# W061B.net
KiCad netlist of a schematic drawn in EAGLE
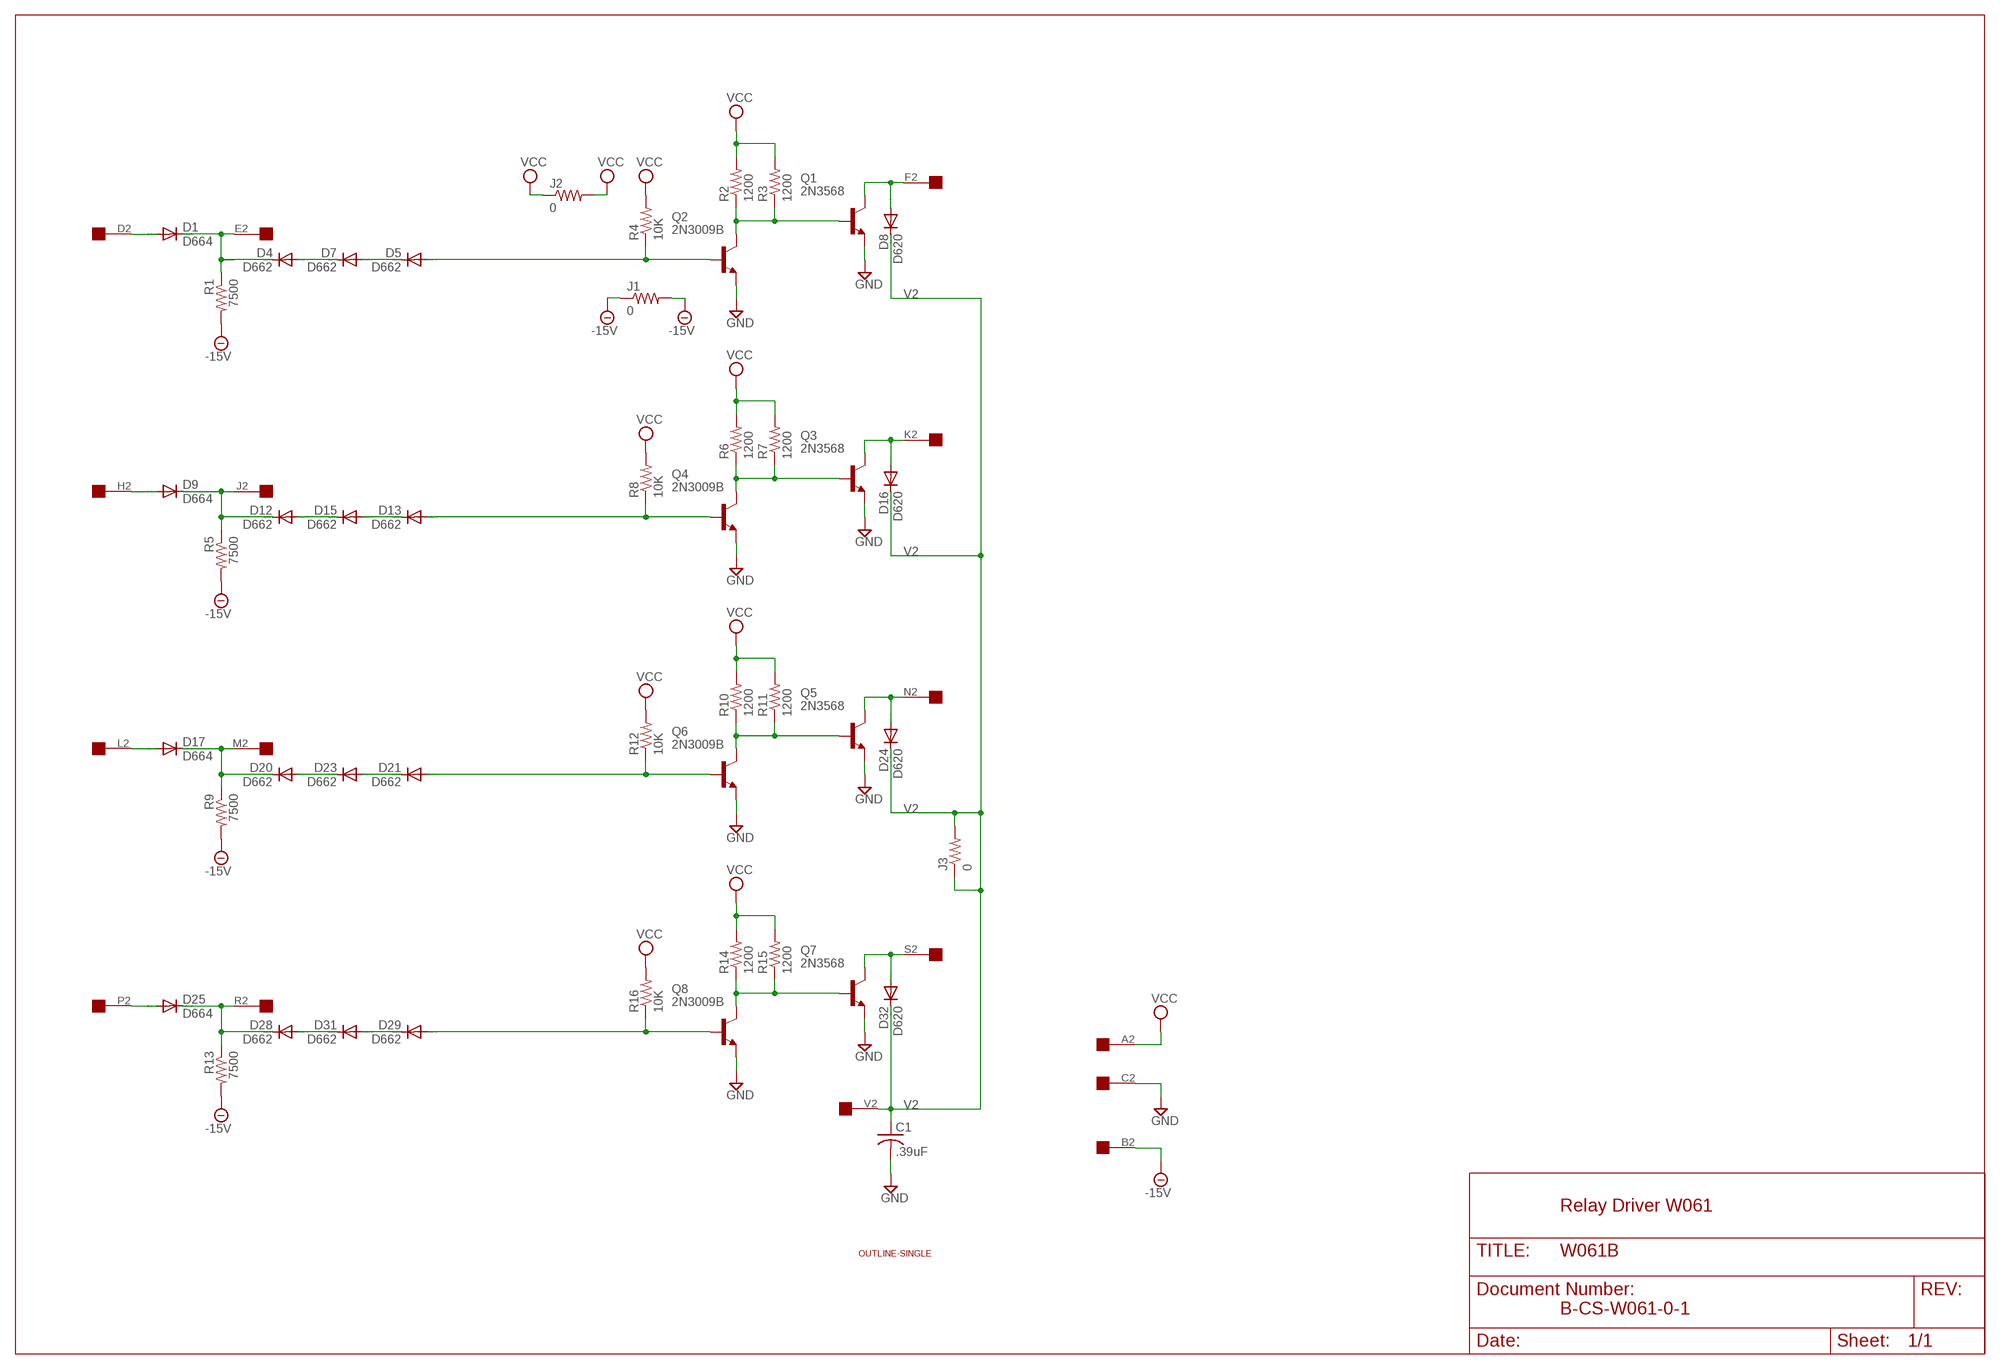
[diagram p0: schematic, sheet 1]

(export (version "E")
  (design (tool "Eeschema 10.0.6"))
  (components
    (comp (ref "C1")
      (value ".39uF")
      (footprint "eagle-import:C375-155X418")
      (libsource (lib "eagle-import") (part "C-US375-155X418"))
    )
    (comp (ref "D1")
      (value "D664")
      (footprint "eagle-import:DO35-10")
      (libsource (lib "eagle-import") (part "DIODE-DO35-10"))
    )
    (comp (ref "D4")
      (value "D662")
      (footprint "eagle-import:DO35-10")
      (libsource (lib "eagle-import") (part "DIODE-DO35-10"))
    )
    (comp (ref "D5")
      (value "D662")
      (footprint "eagle-import:DO35-10")
      (libsource (lib "eagle-import") (part "DIODE-DO35-10"))
    )
    (comp (ref "D7")
      (value "D662")
      (footprint "eagle-import:DO35-10")
      (libsource (lib "eagle-import") (part "DIODE-DO35-10"))
    )
    (comp (ref "D8")
      (value "D620")
      (footprint "eagle-import:DO35-10")
      (libsource (lib "eagle-import") (part "DIODE-DO35-10"))
    )
    (comp (ref "D9")
      (value "D664")
      (footprint "eagle-import:DO35-10")
      (libsource (lib "eagle-import") (part "DIODE-DO35-10"))
    )
    (comp (ref "D12")
      (value "D662")
      (footprint "eagle-import:DO35-10")
      (libsource (lib "eagle-import") (part "DIODE-DO35-10"))
    )
    (comp (ref "D13")
      (value "D662")
      (footprint "eagle-import:DO35-10")
      (libsource (lib "eagle-import") (part "DIODE-DO35-10"))
    )
    (comp (ref "D15")
      (value "D662")
      (footprint "eagle-import:DO35-10")
      (libsource (lib "eagle-import") (part "DIODE-DO35-10"))
    )
    (comp (ref "D16")
      (value "D620")
      (footprint "eagle-import:DO35-10")
      (libsource (lib "eagle-import") (part "DIODE-DO35-10"))
    )
    (comp (ref "D17")
      (value "D664")
      (footprint "eagle-import:DO35-10")
      (libsource (lib "eagle-import") (part "DIODE-DO35-10"))
    )
    (comp (ref "D20")
      (value "D662")
      (footprint "eagle-import:DO35-10")
      (libsource (lib "eagle-import") (part "DIODE-DO35-10"))
    )
    (comp (ref "D21")
      (value "D662")
      (footprint "eagle-import:DO35-10")
      (libsource (lib "eagle-import") (part "DIODE-DO35-10"))
    )
    (comp (ref "D23")
      (value "D662")
      (footprint "eagle-import:DO35-10")
      (libsource (lib "eagle-import") (part "DIODE-DO35-10"))
    )
    (comp (ref "D24")
      (value "D620")
      (footprint "eagle-import:DO35-10")
      (libsource (lib "eagle-import") (part "DIODE-DO35-10"))
    )
    (comp (ref "D25")
      (value "D664")
      (footprint "eagle-import:DO35-10")
      (libsource (lib "eagle-import") (part "DIODE-DO35-10"))
    )
    (comp (ref "D28")
      (value "D662")
      (footprint "eagle-import:DO35-10")
      (libsource (lib "eagle-import") (part "DIODE-DO35-10"))
    )
    (comp (ref "D29")
      (value "D662")
      (footprint "eagle-import:DO35-10")
      (libsource (lib "eagle-import") (part "DIODE-DO35-10"))
    )
    (comp (ref "D31")
      (value "D662")
      (footprint "eagle-import:DO35-10")
      (libsource (lib "eagle-import") (part "DIODE-DO35-10"))
    )
    (comp (ref "D32")
      (value "D620")
      (footprint "eagle-import:DO35-10")
      (libsource (lib "eagle-import") (part "DIODE-DO35-10"))
    )
    (comp (ref "J1")
      (value "0")
      (footprint "eagle-import:0207_10")
      (libsource (lib "eagle-import") (part "R-US_0207/10"))
    )
    (comp (ref "J2")
      (value "0")
      (footprint "eagle-import:0207_10")
      (libsource (lib "eagle-import") (part "R-US_0207/10"))
    )
    (comp (ref "J3")
      (value "0")
      (footprint "eagle-import:0207_10")
      (libsource (lib "eagle-import") (part "R-US_0207/10"))
    )
    (comp (ref "Q1")
      (value "2N3568")
      (footprint "eagle-import:TO5")
      (libsource (lib "eagle-import") (part "-NPN-TO5"))
    )
    (comp (ref "Q2")
      (value "2N3009B")
      (footprint "eagle-import:TO5")
      (libsource (lib "eagle-import") (part "-NPN-TO5"))
    )
    (comp (ref "Q3")
      (value "2N3568")
      (footprint "eagle-import:TO5")
      (libsource (lib "eagle-import") (part "-NPN-TO5"))
    )
    (comp (ref "Q4")
      (value "2N3009B")
      (footprint "eagle-import:TO5")
      (libsource (lib "eagle-import") (part "-NPN-TO5"))
    )
    (comp (ref "Q5")
      (value "2N3568")
      (footprint "eagle-import:TO5")
      (libsource (lib "eagle-import") (part "-NPN-TO5"))
    )
    (comp (ref "Q6")
      (value "2N3009B")
      (footprint "eagle-import:TO5")
      (libsource (lib "eagle-import") (part "-NPN-TO5"))
    )
    (comp (ref "Q7")
      (value "2N3568")
      (footprint "eagle-import:TO5")
      (libsource (lib "eagle-import") (part "-NPN-TO5"))
    )
    (comp (ref "Q8")
      (value "2N3009B")
      (footprint "eagle-import:TO5")
      (libsource (lib "eagle-import") (part "-NPN-TO5"))
    )
    (comp (ref "R1")
      (value "7500")
      (footprint "eagle-import:0207_10")
      (libsource (lib "eagle-import") (part "R-US_0207/10"))
    )
    (comp (ref "R2")
      (value "1200")
      (footprint "eagle-import:0207_10")
      (libsource (lib "eagle-import") (part "R-US_0207/10"))
    )
    (comp (ref "R3")
      (value "1200")
      (footprint "eagle-import:0207_10")
      (libsource (lib "eagle-import") (part "R-US_0207/10"))
    )
    (comp (ref "R4")
      (value "10K")
      (footprint "eagle-import:0207_10")
      (libsource (lib "eagle-import") (part "R-US_0207/10"))
    )
    (comp (ref "R5")
      (value "7500")
      (footprint "eagle-import:0207_10")
      (libsource (lib "eagle-import") (part "R-US_0207/10"))
    )
    (comp (ref "R6")
      (value "1200")
      (footprint "eagle-import:0207_10")
      (libsource (lib "eagle-import") (part "R-US_0207/10"))
    )
    (comp (ref "R7")
      (value "1200")
      (footprint "eagle-import:0207_10")
      (libsource (lib "eagle-import") (part "R-US_0207/10"))
    )
    (comp (ref "R8")
      (value "10K")
      (footprint "eagle-import:0207_10")
      (libsource (lib "eagle-import") (part "R-US_0207/10"))
    )
    (comp (ref "R9")
      (value "7500")
      (footprint "eagle-import:0207_10")
      (libsource (lib "eagle-import") (part "R-US_0207/10"))
    )
    (comp (ref "R10")
      (value "1200")
      (footprint "eagle-import:0207_10")
      (libsource (lib "eagle-import") (part "R-US_0207/10"))
    )
    (comp (ref "R11")
      (value "1200")
      (footprint "eagle-import:0207_10")
      (libsource (lib "eagle-import") (part "R-US_0207/10"))
    )
    (comp (ref "R12")
      (value "10K")
      (footprint "eagle-import:0207_10")
      (libsource (lib "eagle-import") (part "R-US_0207/10"))
    )
    (comp (ref "R13")
      (value "7500")
      (footprint "eagle-import:0207_10")
      (libsource (lib "eagle-import") (part "R-US_0207/10"))
    )
    (comp (ref "R14")
      (value "1200")
      (footprint "eagle-import:0207_10")
      (libsource (lib "eagle-import") (part "R-US_0207/10"))
    )
    (comp (ref "R15")
      (value "1200")
      (footprint "eagle-import:0207_10")
      (libsource (lib "eagle-import") (part "R-US_0207/10"))
    )
    (comp (ref "R16")
      (value "10K")
      (footprint "eagle-import:0207_10")
      (libsource (lib "eagle-import") (part "R-US_0207/10"))
    )
    (comp (ref "U$1")
      (value "OUTLINE-SINGLE")
      (footprint "eagle-import:SINGLE")
      (libsource (lib "eagle-import") (part "OUTLINE-SINGLE"))
    )
    (comp (ref "U$2")
      (value "EDGE-1")
      (footprint "eagle-import:EDGE-CON1")
      (libsource (lib "eagle-import") (part "EDGE-1"))
    )
  )
  (nets
    (net (code "1") (name "-15V") (class "Default")
      (node (ref "J1") (pin "1") (pinfunction "1_1") (pintype "passive"))
      (node (ref "J1") (pin "2") (pinfunction "2_2") (pintype "passive"))
      (node (ref "R1") (pin "2") (pinfunction "2_2") (pintype "passive"))
      (node (ref "R13") (pin "2") (pinfunction "2_2") (pintype "passive"))
      (node (ref "R5") (pin "2") (pinfunction "2_2") (pintype "passive"))
      (node (ref "R9") (pin "2") (pinfunction "2_2") (pintype "passive"))
      (node (ref "U$2") (pin "B2") (pinfunction "1_B2") (pintype "bidirectional"))
    )
    (net (code "2") (name "/V2") (class "Default")
      (node (ref "C1") (pin "1") (pinfunction "1_1") (pintype "passive"))
      (node (ref "D16") (pin "C") (pinfunction "C_C") (pintype "passive"))
      (node (ref "D24") (pin "C") (pinfunction "C_C") (pintype "passive"))
      (node (ref "D32") (pin "C") (pinfunction "C_C") (pintype "passive"))
      (node (ref "D8") (pin "C") (pinfunction "C_C") (pintype "passive"))
      (node (ref "J3") (pin "1") (pinfunction "1_1") (pintype "passive"))
      (node (ref "J3") (pin "2") (pinfunction "2_2") (pintype "passive"))
      (node (ref "U$2") (pin "V2") (pinfunction "1_V2") (pintype "bidirectional"))
    )
    (net (code "3") (name "GND") (class "Default")
      (node (ref "C1") (pin "2") (pinfunction "2_2") (pintype "passive"))
      (node (ref "Q1") (pin "1") (pinfunction "E_1") (pintype "passive"))
      (node (ref "Q2") (pin "1") (pinfunction "E_1") (pintype "passive"))
      (node (ref "Q3") (pin "1") (pinfunction "E_1") (pintype "passive"))
      (node (ref "Q4") (pin "1") (pinfunction "E_1") (pintype "passive"))
      (node (ref "Q5") (pin "1") (pinfunction "E_1") (pintype "passive"))
      (node (ref "Q6") (pin "1") (pinfunction "E_1") (pintype "passive"))
      (node (ref "Q7") (pin "1") (pinfunction "E_1") (pintype "passive"))
      (node (ref "Q8") (pin "1") (pinfunction "E_1") (pintype "passive"))
      (node (ref "U$2") (pin "C2") (pinfunction "1_C2") (pintype "bidirectional"))
    )
    (net (code "4") (name "Net-(D4-PadA)") (class "Default")
      (node (ref "D4") (pin "A") (pinfunction "A_A") (pintype "passive"))
      (node (ref "D7") (pin "C") (pinfunction "C_C") (pintype "passive"))
    )
    (net (code "5") (name "Net-(D5-PadC)") (class "Default")
      (node (ref "D5") (pin "C") (pinfunction "C_C") (pintype "passive"))
      (node (ref "D7") (pin "A") (pinfunction "A_A") (pintype "passive"))
    )
    (net (code "6") (name "Net-(D12-PadA)") (class "Default")
      (node (ref "D12") (pin "A") (pinfunction "A_A") (pintype "passive"))
      (node (ref "D15") (pin "C") (pinfunction "C_C") (pintype "passive"))
    )
    (net (code "7") (name "Net-(D13-PadC)") (class "Default")
      (node (ref "D13") (pin "C") (pinfunction "C_C") (pintype "passive"))
      (node (ref "D15") (pin "A") (pinfunction "A_A") (pintype "passive"))
    )
    (net (code "8") (name "Net-(D20-PadA)") (class "Default")
      (node (ref "D20") (pin "A") (pinfunction "A_A") (pintype "passive"))
      (node (ref "D23") (pin "C") (pinfunction "C_C") (pintype "passive"))
    )
    (net (code "9") (name "Net-(D21-PadC)") (class "Default")
      (node (ref "D21") (pin "C") (pinfunction "C_C") (pintype "passive"))
      (node (ref "D23") (pin "A") (pinfunction "A_A") (pintype "passive"))
    )
    (net (code "10") (name "Net-(D28-PadA)") (class "Default")
      (node (ref "D28") (pin "A") (pinfunction "A_A") (pintype "passive"))
      (node (ref "D31") (pin "C") (pinfunction "C_C") (pintype "passive"))
    )
    (net (code "11") (name "Net-(D29-PadC)") (class "Default")
      (node (ref "D29") (pin "C") (pinfunction "C_C") (pintype "passive"))
      (node (ref "D31") (pin "A") (pinfunction "A_A") (pintype "passive"))
    )
    (net (code "12") (name "Net-(Q1-B)") (class "Default")
      (node (ref "Q1") (pin "2") (pinfunction "B_2") (pintype "passive"))
      (node (ref "Q2") (pin "3") (pinfunction "C_3") (pintype "passive"))
      (node (ref "R2") (pin "1") (pinfunction "1_1") (pintype "passive"))
      (node (ref "R3") (pin "1") (pinfunction "1_1") (pintype "passive"))
    )
    (net (code "13") (name "Net-(Q1-C)") (class "Default")
      (node (ref "D8") (pin "A") (pinfunction "A_A") (pintype "passive"))
      (node (ref "Q1") (pin "3") (pinfunction "C_3") (pintype "passive"))
      (node (ref "U$2") (pin "F2") (pinfunction "1_F2") (pintype "bidirectional"))
    )
    (net (code "14") (name "Net-(Q2-B)") (class "Default")
      (node (ref "D5") (pin "A") (pinfunction "A_A") (pintype "passive"))
      (node (ref "Q2") (pin "2") (pinfunction "B_2") (pintype "passive"))
      (node (ref "R4") (pin "1") (pinfunction "1_1") (pintype "passive"))
    )
    (net (code "15") (name "Net-(Q3-B)") (class "Default")
      (node (ref "Q3") (pin "2") (pinfunction "B_2") (pintype "passive"))
      (node (ref "Q4") (pin "3") (pinfunction "C_3") (pintype "passive"))
      (node (ref "R6") (pin "1") (pinfunction "1_1") (pintype "passive"))
      (node (ref "R7") (pin "1") (pinfunction "1_1") (pintype "passive"))
    )
    (net (code "16") (name "Net-(Q3-C)") (class "Default")
      (node (ref "D16") (pin "A") (pinfunction "A_A") (pintype "passive"))
      (node (ref "Q3") (pin "3") (pinfunction "C_3") (pintype "passive"))
      (node (ref "U$2") (pin "K2") (pinfunction "1_K2") (pintype "bidirectional"))
    )
    (net (code "17") (name "Net-(Q4-B)") (class "Default")
      (node (ref "D13") (pin "A") (pinfunction "A_A") (pintype "passive"))
      (node (ref "Q4") (pin "2") (pinfunction "B_2") (pintype "passive"))
      (node (ref "R8") (pin "1") (pinfunction "1_1") (pintype "passive"))
    )
    (net (code "18") (name "Net-(Q5-B)") (class "Default")
      (node (ref "Q5") (pin "2") (pinfunction "B_2") (pintype "passive"))
      (node (ref "Q6") (pin "3") (pinfunction "C_3") (pintype "passive"))
      (node (ref "R10") (pin "1") (pinfunction "1_1") (pintype "passive"))
      (node (ref "R11") (pin "1") (pinfunction "1_1") (pintype "passive"))
    )
    (net (code "19") (name "Net-(Q5-C)") (class "Default")
      (node (ref "D24") (pin "A") (pinfunction "A_A") (pintype "passive"))
      (node (ref "Q5") (pin "3") (pinfunction "C_3") (pintype "passive"))
      (node (ref "U$2") (pin "N2") (pinfunction "1_N2") (pintype "bidirectional"))
    )
    (net (code "20") (name "Net-(Q6-B)") (class "Default")
      (node (ref "D21") (pin "A") (pinfunction "A_A") (pintype "passive"))
      (node (ref "Q6") (pin "2") (pinfunction "B_2") (pintype "passive"))
      (node (ref "R12") (pin "1") (pinfunction "1_1") (pintype "passive"))
    )
    (net (code "21") (name "Net-(Q7-B)") (class "Default")
      (node (ref "Q7") (pin "2") (pinfunction "B_2") (pintype "passive"))
      (node (ref "Q8") (pin "3") (pinfunction "C_3") (pintype "passive"))
      (node (ref "R14") (pin "1") (pinfunction "1_1") (pintype "passive"))
      (node (ref "R15") (pin "1") (pinfunction "1_1") (pintype "passive"))
    )
    (net (code "22") (name "Net-(Q7-C)") (class "Default")
      (node (ref "D32") (pin "A") (pinfunction "A_A") (pintype "passive"))
      (node (ref "Q7") (pin "3") (pinfunction "C_3") (pintype "passive"))
      (node (ref "U$2") (pin "S2") (pinfunction "1_S2") (pintype "bidirectional"))
    )
    (net (code "23") (name "Net-(Q8-B)") (class "Default")
      (node (ref "D29") (pin "A") (pinfunction "A_A") (pintype "passive"))
      (node (ref "Q8") (pin "2") (pinfunction "B_2") (pintype "passive"))
      (node (ref "R16") (pin "1") (pinfunction "1_1") (pintype "passive"))
    )
    (net (code "24") (name "Net-(U$2D-1)") (class "Default")
      (node (ref "D1") (pin "A") (pinfunction "A_A") (pintype "passive"))
      (node (ref "U$2") (pin "D2") (pinfunction "1_D2") (pintype "bidirectional"))
    )
    (net (code "25") (name "Net-(U$2E-1)") (class "Default")
      (node (ref "D1") (pin "C") (pinfunction "C_C") (pintype "passive"))
      (node (ref "D4") (pin "C") (pinfunction "C_C") (pintype "passive"))
      (node (ref "R1") (pin "1") (pinfunction "1_1") (pintype "passive"))
      (node (ref "U$2") (pin "E2") (pinfunction "1_E2") (pintype "bidirectional"))
    )
    (net (code "26") (name "Net-(U$2G-1)") (class "Default")
      (node (ref "D9") (pin "A") (pinfunction "A_A") (pintype "passive"))
      (node (ref "U$2") (pin "H2") (pinfunction "1_H2") (pintype "bidirectional"))
    )
    (net (code "27") (name "Net-(U$2H-1)") (class "Default")
      (node (ref "D12") (pin "C") (pinfunction "C_C") (pintype "passive"))
      (node (ref "D9") (pin "C") (pinfunction "C_C") (pintype "passive"))
      (node (ref "R5") (pin "1") (pinfunction "1_1") (pintype "passive"))
      (node (ref "U$2") (pin "J2") (pinfunction "1_J2") (pintype "bidirectional"))
    )
    (net (code "28") (name "Net-(U$2J-1)") (class "Default")
      (node (ref "D17") (pin "A") (pinfunction "A_A") (pintype "passive"))
      (node (ref "U$2") (pin "L2") (pinfunction "1_L2") (pintype "bidirectional"))
    )
    (net (code "29") (name "Net-(U$2K-1)") (class "Default")
      (node (ref "D17") (pin "C") (pinfunction "C_C") (pintype "passive"))
      (node (ref "D20") (pin "C") (pinfunction "C_C") (pintype "passive"))
      (node (ref "R9") (pin "1") (pinfunction "1_1") (pintype "passive"))
      (node (ref "U$2") (pin "M2") (pinfunction "1_M2") (pintype "bidirectional"))
    )
    (net (code "30") (name "Net-(U$2M-1)") (class "Default")
      (node (ref "D25") (pin "A") (pinfunction "A_A") (pintype "passive"))
      (node (ref "U$2") (pin "P2") (pinfunction "1_P2") (pintype "bidirectional"))
    )
    (net (code "31") (name "Net-(U$2N-1)") (class "Default")
      (node (ref "D25") (pin "C") (pinfunction "C_C") (pintype "passive"))
      (node (ref "D28") (pin "C") (pinfunction "C_C") (pintype "passive"))
      (node (ref "R13") (pin "1") (pinfunction "1_1") (pintype "passive"))
      (node (ref "U$2") (pin "R2") (pinfunction "1_R2") (pintype "bidirectional"))
    )
    (net (code "32") (name "VCC") (class "Default")
      (node (ref "J2") (pin "1") (pinfunction "1_1") (pintype "passive"))
      (node (ref "J2") (pin "2") (pinfunction "2_2") (pintype "passive"))
      (node (ref "R10") (pin "2") (pinfunction "2_2") (pintype "passive"))
      (node (ref "R11") (pin "2") (pinfunction "2_2") (pintype "passive"))
      (node (ref "R12") (pin "2") (pinfunction "2_2") (pintype "passive"))
      (node (ref "R14") (pin "2") (pinfunction "2_2") (pintype "passive"))
      (node (ref "R15") (pin "2") (pinfunction "2_2") (pintype "passive"))
      (node (ref "R16") (pin "2") (pinfunction "2_2") (pintype "passive"))
      (node (ref "R2") (pin "2") (pinfunction "2_2") (pintype "passive"))
      (node (ref "R3") (pin "2") (pinfunction "2_2") (pintype "passive"))
      (node (ref "R4") (pin "2") (pinfunction "2_2") (pintype "passive"))
      (node (ref "R6") (pin "2") (pinfunction "2_2") (pintype "passive"))
      (node (ref "R7") (pin "2") (pinfunction "2_2") (pintype "passive"))
      (node (ref "R8") (pin "2") (pinfunction "2_2") (pintype "passive"))
      (node (ref "U$2") (pin "A2") (pinfunction "1_A2") (pintype "bidirectional"))
    )
  )
)
